# Output_Mixer.net
KiCad netlist of a schematic drawn in Altium Designer
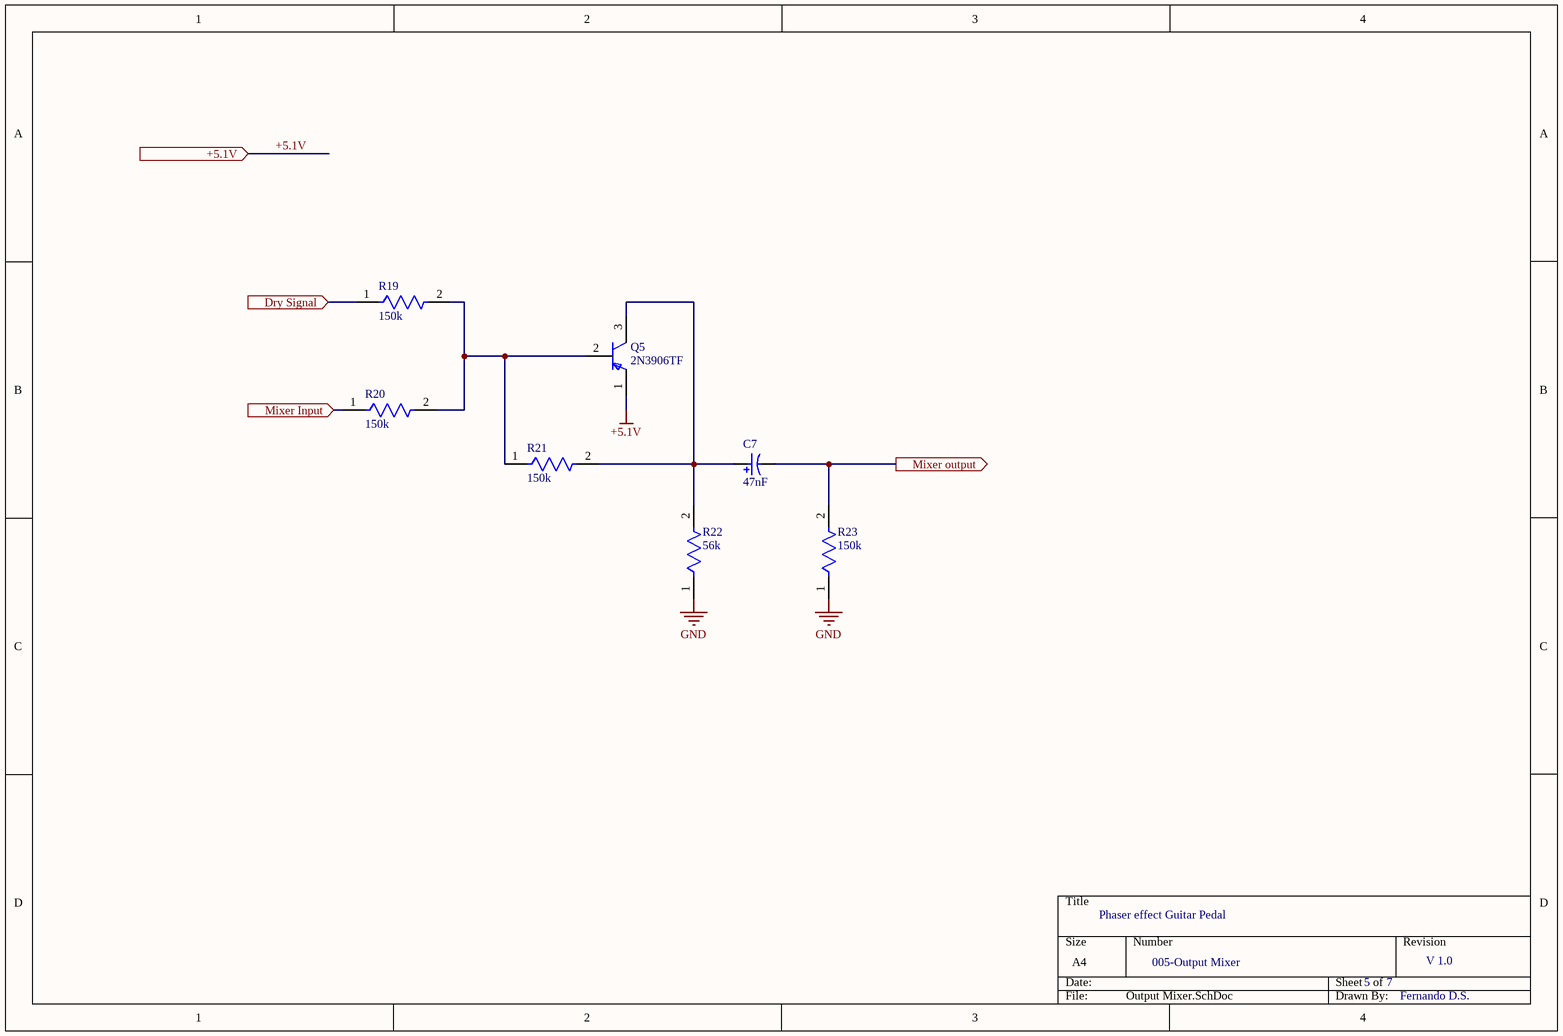
[diagram p0: Output Mixer.SchDoc]

(export (version "E")
  (design (tool "Eeschema 10.0.6"))
  (components
    (comp (ref "C7")
      (value "47nF")
      (footprint "NIC-PLF-10x13-2_V")
      (description "Aluminum Electrolytic Capacitor, 470 uF +/-20%, 10 V, -55 to 105 degC, 2-Pin THD, RoHS")
      (fields (field (name "MANUFACTURER") "Nichicon") (field (name "PARTNUMBER") "PLF1A471MDO1"))
      (libsource (lib "Altium Content Vault") (part "NIC-CAP-P-2"))
    )
    (comp (ref "Q5")
      (value "2N3906TF")
      (footprint "FP-135AR-MFG")
      (description "2N3906TF Small Signal Bipolar Transistor, 0.2A I(C), 40V V(BR)CEO, 1-Element, PNP, Silicon, TO-92")
      (libsource (lib "Altium Content Vault") (part "40d2b7e180a7bcff784209620afba3e"))
    )
    (comp (ref "R19")
      (value "150k")
      (footprint "FP-MRS25-MFG")
      (fields (field (name "TOLERANCE") "1%"))
      (libsource (lib "Altium Content Vault") (part "1029c3af85768c4190bb7ad29bc67b5"))
    )
    (comp (ref "R20")
      (value "150k")
      (footprint "FP-MRS25-MFG")
      (fields (field (name "TOLERANCE") "1%"))
      (libsource (lib "Altium Content Vault") (part "1029c3af85768c4190bb7ad29bc67b5"))
    )
    (comp (ref "R21")
      (value "150k")
      (footprint "FP-MRS25-MFG")
      (fields (field (name "TOLERANCE") "1%"))
      (libsource (lib "Altium Content Vault") (part "1029c3af85768c4190bb7ad29bc67b5"))
    )
    (comp (ref "R22")
      (value "56k")
      (footprint "FP-MRS25-MFG")
      (fields (field (name "TOLERANCE") "1%"))
      (libsource (lib "Altium Content Vault") (part "1029c3af85768c4190bb7ad29bc67b5"))
    )
    (comp (ref "R23")
      (value "150k")
      (footprint "FP-MRS25-MFG")
      (fields (field (name "TOLERANCE") "1%"))
      (libsource (lib "Altium Content Vault") (part "1029c3af85768c4190bb7ad29bc67b5"))
    )
  )
  (nets
    (net (code "1") (name "+5.1V") (class "Default")
      (node (ref "Q5") (pin "1") (pinfunction "E_1") (pintype "passive"))
    )
    (net (code "2") (name "/Dry Signal") (class "Default")
      (node (ref "R19") (pin "1") (pinfunction "1_1") (pintype "passive"))
    )
    (net (code "3") (name "/Mixer Input") (class "Default")
      (node (ref "R20") (pin "1") (pinfunction "1_1") (pintype "passive"))
    )
    (net (code "4") (name "/Mixer output") (class "Default")
      (node (ref "C7") (pin "2") (pinfunction "2_2") (pintype "passive"))
      (node (ref "R23") (pin "2") (pinfunction "2_2") (pintype "passive"))
    )
    (net (code "5") (name "GND") (class "Default")
      (node (ref "R22") (pin "1") (pinfunction "1_1") (pintype "passive"))
      (node (ref "R23") (pin "1") (pinfunction "1_1") (pintype "passive"))
    )
    (net (code "6") (name "Net-(Q5-B)") (class "Default")
      (node (ref "Q5") (pin "2") (pinfunction "B_2") (pintype "passive"))
      (node (ref "R19") (pin "2") (pinfunction "2_2") (pintype "passive"))
      (node (ref "R20") (pin "2") (pinfunction "2_2") (pintype "passive"))
      (node (ref "R21") (pin "1") (pinfunction "1_1") (pintype "passive"))
    )
    (net (code "7") (name "Net-(Q5-C)") (class "Default")
      (node (ref "C7") (pin "1") (pinfunction "1_1") (pintype "passive"))
      (node (ref "Q5") (pin "3") (pinfunction "C_3") (pintype "passive"))
      (node (ref "R21") (pin "2") (pinfunction "2_2") (pintype "passive"))
      (node (ref "R22") (pin "2") (pinfunction "2_2") (pintype "passive"))
    )
  )
)
